# card.net
KiCad netlist of a schematic drawn in EAGLE
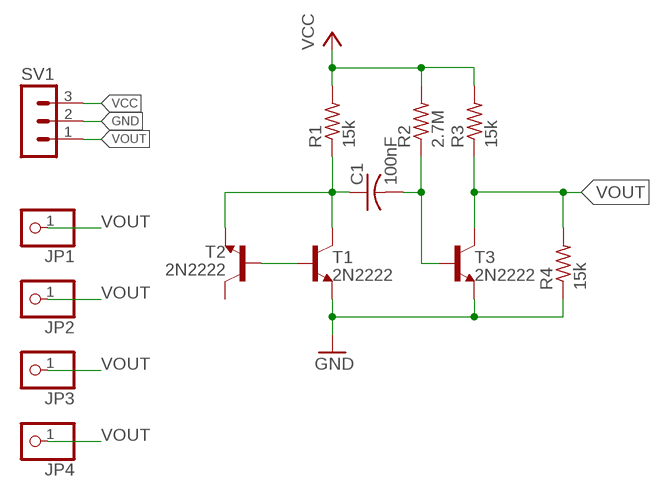
[diagram p0: schematic, sheet 1]

(export (version "E")
  (design (tool "Eeschema 10.0.6"))
  (components
    (comp (ref "C1")
      (value "100nF")
      (footprint "eagle-import:C025-025X050")
      (libsource (lib "eagle-import") (part "C-US025-025X050"))
    )
    (comp (ref "JP1")
      (value "PINHD-1X1")
      (footprint "eagle-import:1X01")
      (libsource (lib "eagle-import") (part "PINHD-1X1"))
    )
    (comp (ref "JP2")
      (value "PINHD-1X1")
      (footprint "eagle-import:1X01")
      (libsource (lib "eagle-import") (part "PINHD-1X1"))
    )
    (comp (ref "JP3")
      (value "PINHD-1X1")
      (footprint "eagle-import:1X01")
      (libsource (lib "eagle-import") (part "PINHD-1X1"))
    )
    (comp (ref "JP4")
      (value "PINHD-1X1")
      (footprint "eagle-import:1X01")
      (libsource (lib "eagle-import") (part "PINHD-1X1"))
    )
    (comp (ref "R1")
      (value "15k")
      (footprint "eagle-import:0204_7")
      (libsource (lib "eagle-import") (part "R-US_0204/7"))
    )
    (comp (ref "R2")
      (value "2.7M")
      (footprint "eagle-import:0204_7")
      (libsource (lib "eagle-import") (part "R-US_0204/7"))
    )
    (comp (ref "R3")
      (value "15k")
      (footprint "eagle-import:0204_7")
      (libsource (lib "eagle-import") (part "R-US_0204/7"))
    )
    (comp (ref "R4")
      (value "15k")
      (footprint "eagle-import:0204_7")
      (libsource (lib "eagle-import") (part "R-US_0204/7"))
    )
    (comp (ref "SV1")
      (value "MA03-1")
      (footprint "eagle-import:MA03-1")
      (libsource (lib "eagle-import") (part "MA03-1"))
    )
    (comp (ref "T1")
      (value "2N2222")
      (footprint "eagle-import:TO18")
      (libsource (lib "eagle-import") (part "2N2222"))
    )
    (comp (ref "T2")
      (value "2N2222")
      (footprint "eagle-import:TO18")
      (libsource (lib "eagle-import") (part "2N2222"))
    )
    (comp (ref "T3")
      (value "2N2222")
      (footprint "eagle-import:TO18")
      (libsource (lib "eagle-import") (part "2N2222"))
    )
  )
  (nets
    (net (code "1") (name "GND") (class "Default")
      (node (ref "R4") (pin "1") (pinfunction "1_1") (pintype "passive"))
      (node (ref "SV1") (pin "2") (pinfunction "2_2") (pintype "passive"))
      (node (ref "T1") (pin "1") (pinfunction "E_1") (pintype "passive"))
      (node (ref "T3") (pin "1") (pinfunction "E_1") (pintype "passive"))
    )
    (net (code "2") (name "Net-(T1-B)") (class "Default")
      (node (ref "T1") (pin "2") (pinfunction "B_2") (pintype "passive"))
      (node (ref "T2") (pin "2") (pinfunction "B_2") (pintype "passive"))
    )
    (net (code "3") (name "Net-(T1-C)") (class "Default")
      (node (ref "C1") (pin "1") (pinfunction "1_1") (pintype "passive"))
      (node (ref "R1") (pin "1") (pinfunction "1_1") (pintype "passive"))
      (node (ref "T1") (pin "3") (pinfunction "C_3") (pintype "passive"))
      (node (ref "T2") (pin "1") (pinfunction "E_1") (pintype "passive"))
    )
    (net (code "4") (name "Net-(T3-B)") (class "Default")
      (node (ref "C1") (pin "2") (pinfunction "2_2") (pintype "passive"))
      (node (ref "R2") (pin "1") (pinfunction "1_1") (pintype "passive"))
      (node (ref "T3") (pin "2") (pinfunction "B_2") (pintype "passive"))
    )
    (net (code "5") (name "VCC") (class "Default")
      (node (ref "R1") (pin "2") (pinfunction "2_2") (pintype "passive"))
      (node (ref "R2") (pin "2") (pinfunction "2_2") (pintype "passive"))
      (node (ref "R3") (pin "2") (pinfunction "2_2") (pintype "passive"))
      (node (ref "SV1") (pin "3") (pinfunction "3_3") (pintype "passive"))
    )
    (net (code "6") (name "VOUT") (class "Default")
      (node (ref "JP1") (pin "1") (pinfunction "1_1") (pintype "passive"))
      (node (ref "JP2") (pin "1") (pinfunction "1_1") (pintype "passive"))
      (node (ref "JP3") (pin "1") (pinfunction "1_1") (pintype "passive"))
      (node (ref "JP4") (pin "1") (pinfunction "1_1") (pintype "passive"))
      (node (ref "R3") (pin "1") (pinfunction "1_1") (pintype "passive"))
      (node (ref "R4") (pin "2") (pinfunction "2_2") (pintype "passive"))
      (node (ref "SV1") (pin "1") (pinfunction "1_1") (pintype "passive"))
      (node (ref "T3") (pin "3") (pinfunction "C_3") (pintype "passive"))
    )
    (net (code "7") (name "unconnected-(T2-C-Pad3)") (class "Default")
      (node (ref "T2") (pin "3") (pinfunction "C_3") (pintype "passive"))
    )
  )
)
